# Interfaces.net
KiCad netlist of a schematic drawn in Altium Designer
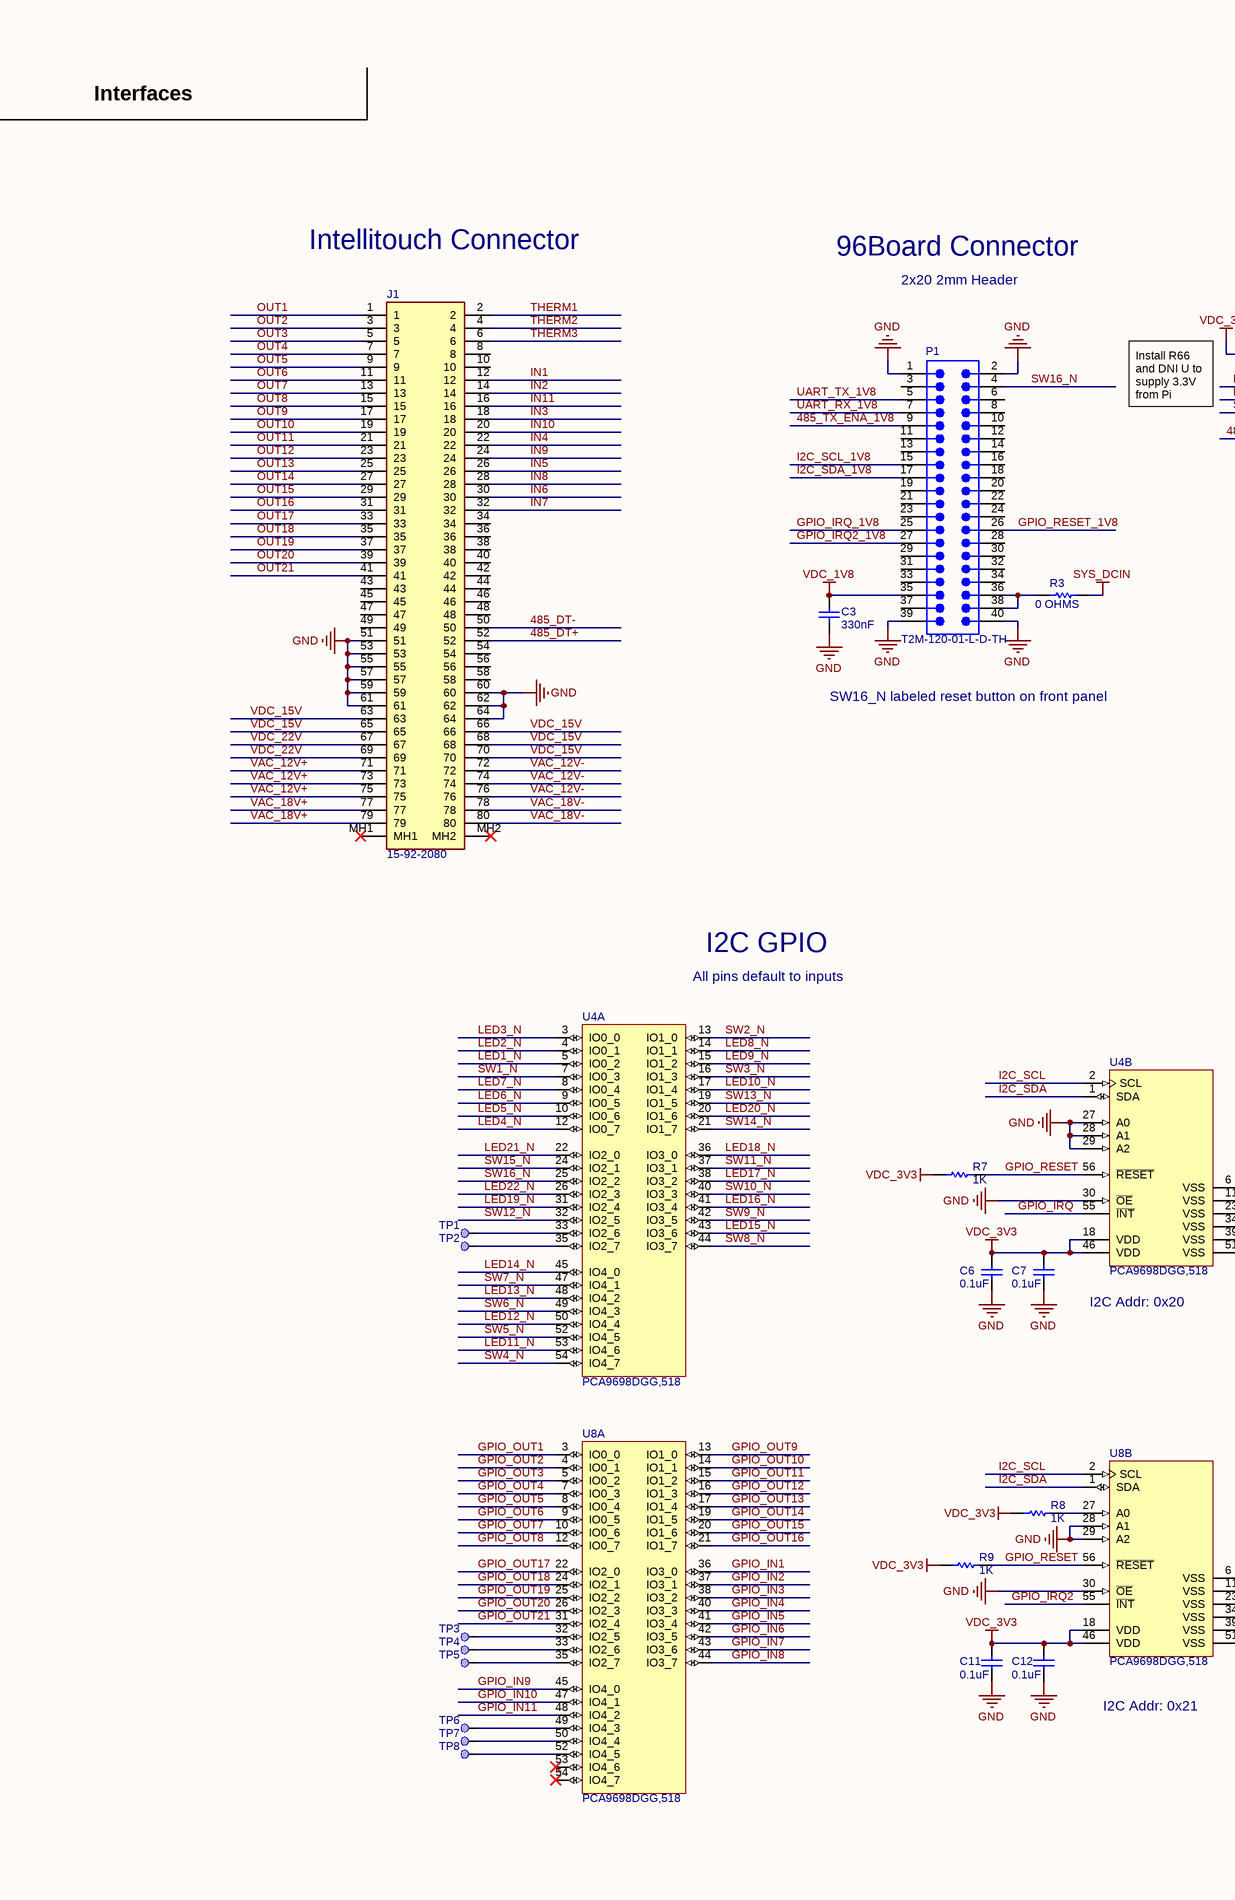
[diagram p0: Interfaces.SchDoc, left]
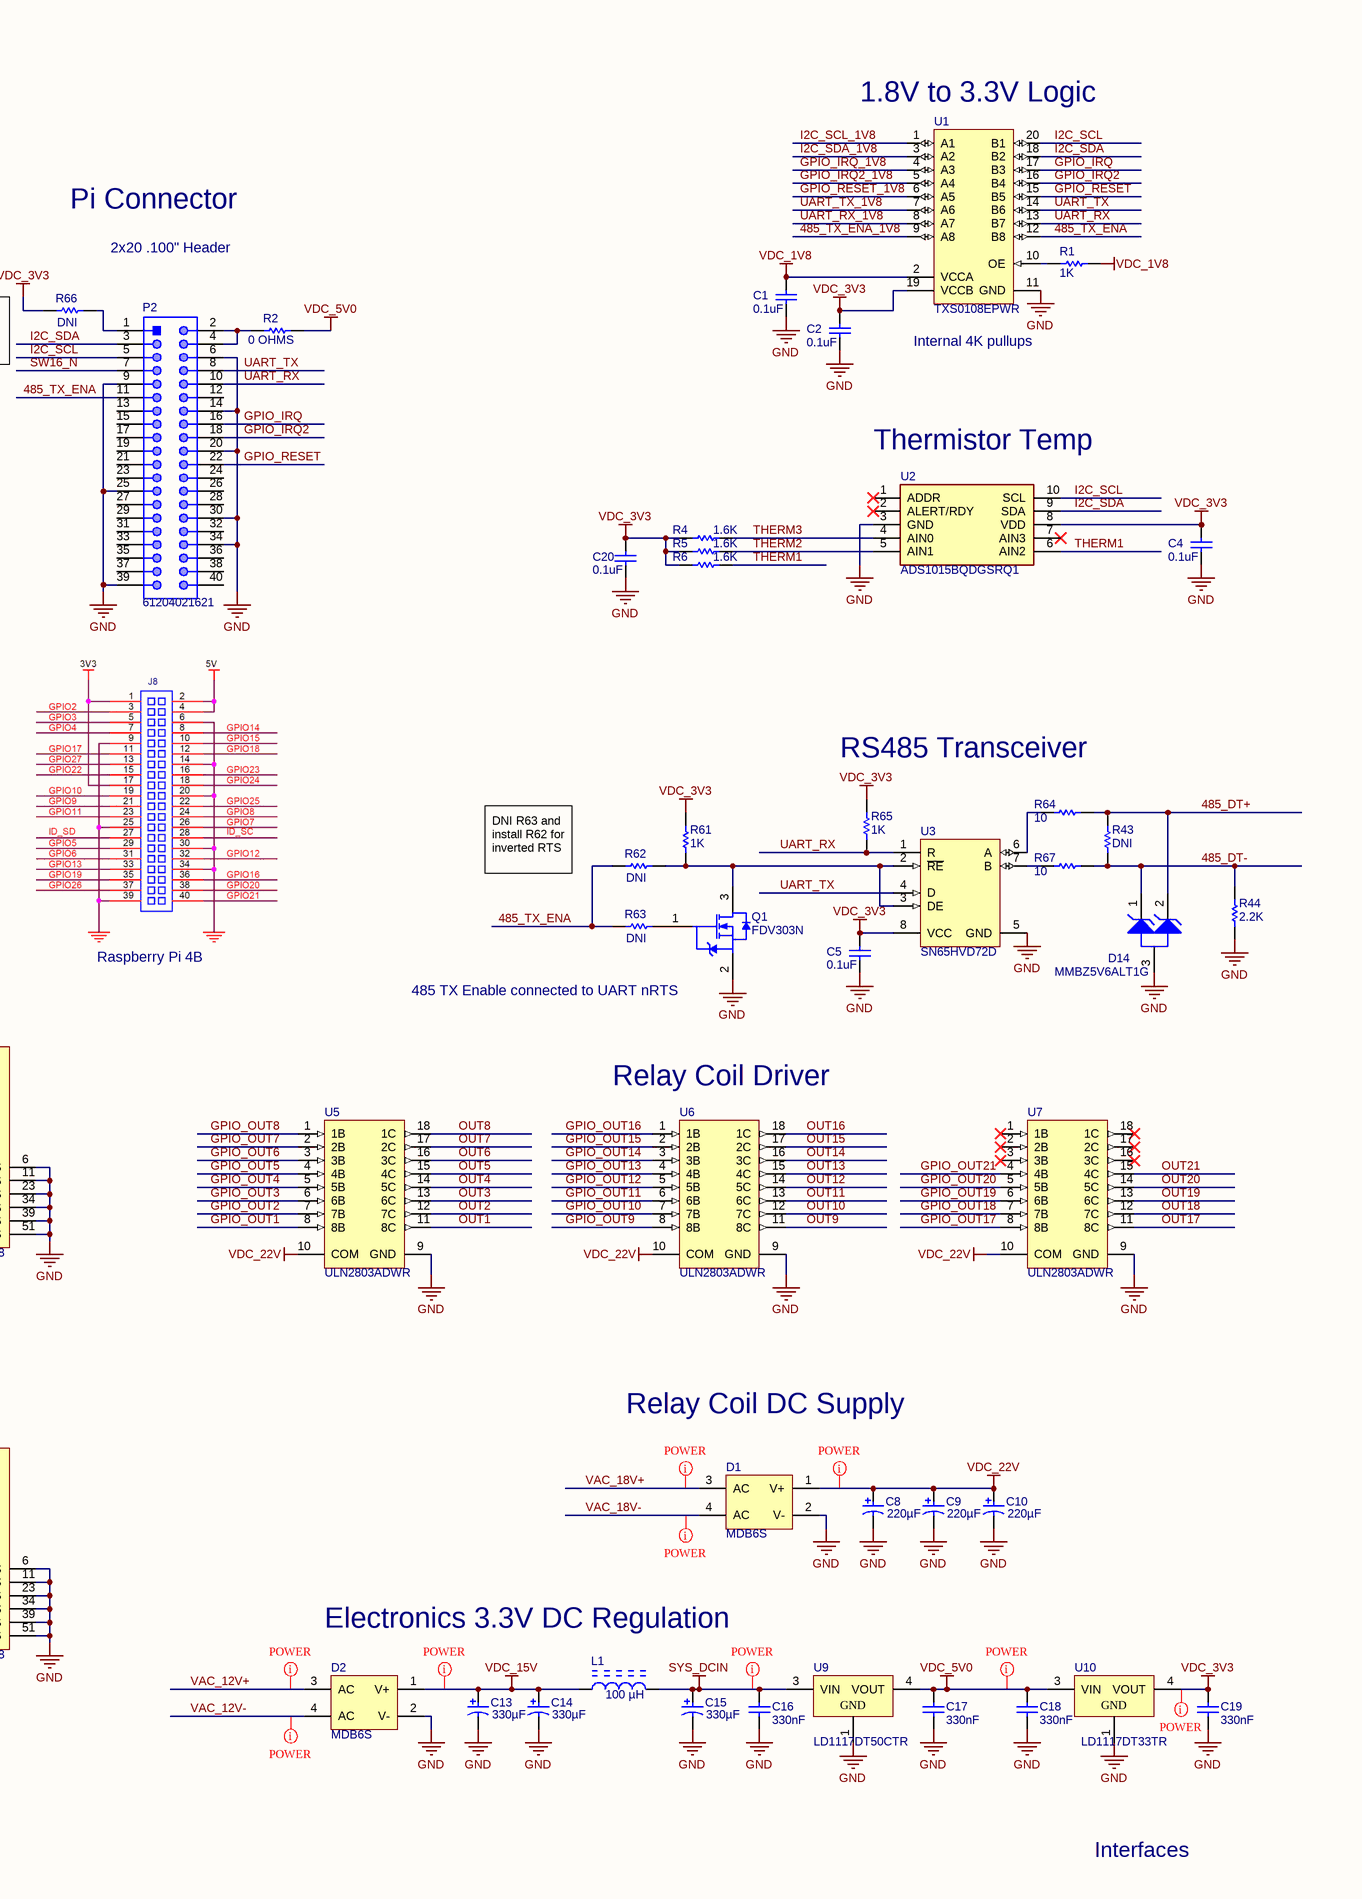
[diagram p1: Interfaces.SchDoc, right]

(export (version "E")
  (design (tool "Eeschema 10.0.6"))
  (components
    (comp (ref "C1")
      (value "0.1uF")
      (footprint "CAPC1608X87X35NL15T15")
      (fields (field (name "PART NUMBER") "C0603X104K5RACTU") (field (name "MANUFACTURER") "Kemet"))
      (libsource (lib "Altium Content Vault") (part "CAP"))
    )
    (comp (ref "C2")
      (value "0.1uF")
      (footprint "CAPC1608X87X35NL15T15")
      (fields (field (name "PART NUMBER") "C0603X104K5RACTU") (field (name "MANUFACTURER") "Kemet"))
      (libsource (lib "Altium Content Vault") (part "CAP"))
    )
    (comp (ref "C3")
      (value "330nF")
      (footprint "CAPC0805(2012)100_M")
      (description "CAP 330nF 50V ±10% 0805 (2012 Metric) Thickness 1mm SMD")
      (fields (field (name "TOLERANCE") "Â±10%") (field (name "Comment") "CAP 330nF 50V 0805(2012)"))
      (libsource (lib "Altium Content Vault") (part "CAP"))
    )
    (comp (ref "C4")
      (value "0.1uF")
      (footprint "CAPC1608X87X35NL15T15")
      (fields (field (name "PART NUMBER") "C0603X104K5RACTU") (field (name "MANUFACTURER") "Kemet"))
      (libsource (lib "Altium Content Vault") (part "CAP"))
    )
    (comp (ref "C5")
      (value "0.1uF")
      (footprint "CAPC1608X87X35NL15T15")
      (fields (field (name "PART NUMBER") "C0603X104K5RACTU") (field (name "MANUFACTURER") "Kemet"))
      (libsource (lib "Altium Content Vault") (part "CAP"))
    )
    (comp (ref "C6")
      (value "0.1uF")
      (footprint "CAPC1608X87X35NL15T15")
      (fields (field (name "PART NUMBER") "C0603X104K5RACTU") (field (name "MANUFACTURER") "Kemet"))
      (libsource (lib "Altium Content Vault") (part "CAP"))
    )
    (comp (ref "C7")
      (value "0.1uF")
      (footprint "CAPC1608X87X35NL15T15")
      (fields (field (name "PART NUMBER") "C0603X104K5RACTU") (field (name "MANUFACTURER") "Kemet"))
      (libsource (lib "Altium Content Vault") (part "CAP"))
    )
    (comp (ref "C8")
      (value "EEE-1HA221P")
      (footprint "PNSC-EEE-1HA221P_L")
      (fields (field (name "MANUFACTURER") "Panasonic") (field (name "CAPACITANCE") "220µF"))
      (libsource (lib "Altium Content Vault") (part "CAP-P-2"))
    )
    (comp (ref "C9")
      (value "EEE-1HA221P")
      (footprint "PNSC-EEE-1HA221P_L")
      (fields (field (name "MANUFACTURER") "Panasonic") (field (name "CAPACITANCE") "220µF"))
      (libsource (lib "Altium Content Vault") (part "CAP-P-2"))
    )
    (comp (ref "C10")
      (value "EEE-1HA221P")
      (footprint "PNSC-EEE-1HA221P_L")
      (fields (field (name "MANUFACTURER") "Panasonic") (field (name "CAPACITANCE") "220µF"))
      (libsource (lib "Altium Content Vault") (part "CAP-P-2"))
    )
    (comp (ref "C11")
      (value "0.1uF")
      (footprint "CAPC1608X87X35NL15T15")
      (fields (field (name "PART NUMBER") "C0603X104K5RACTU") (field (name "MANUFACTURER") "Kemet"))
      (libsource (lib "Altium Content Vault") (part "CAP"))
    )
    (comp (ref "C12")
      (value "0.1uF")
      (footprint "CAPC1608X87X35NL15T15")
      (fields (field (name "PART NUMBER") "C0603X104K5RACTU") (field (name "MANUFACTURER") "Kemet"))
      (libsource (lib "Altium Content Vault") (part "CAP"))
    )
    (comp (ref "C13")
      (value "EEE-FK1V331P")
      (footprint "PNSC-EEE-FK1V331P_L")
      (description "Aluminum Electrolytic Capacitor, 330 uF, 35 V, -55 to 105 degC, 2-Pin CAPAE, RoHS, Tape and Reel")
      (fields (field (name "CAPACITANCE") "330µF") (field (name "MANUFACTURER") "Panasonic"))
      (libsource (lib "Altium Content Vault") (part "CAP-P-2"))
    )
    (comp (ref "C14")
      (value "EEE-FK1V331P")
      (footprint "PNSC-EEE-FK1V331P_L")
      (description "Aluminum Electrolytic Capacitor, 330 uF, 35 V, -55 to 105 degC, 2-Pin CAPAE, RoHS, Tape and Reel")
      (fields (field (name "CAPACITANCE") "330µF") (field (name "MANUFACTURER") "Panasonic"))
      (libsource (lib "Altium Content Vault") (part "CAP-P-2"))
    )
    (comp (ref "C15")
      (value "EEE-FK1V331P")
      (footprint "PNSC-EEE-FK1V331P_L")
      (description "Aluminum Electrolytic Capacitor, 330 uF, 35 V, -55 to 105 degC, 2-Pin CAPAE, RoHS, Tape and Reel")
      (fields (field (name "CAPACITANCE") "330µF") (field (name "MANUFACTURER") "Panasonic"))
      (libsource (lib "Altium Content Vault") (part "CAP-P-2"))
    )
    (comp (ref "C16")
      (value "330nF")
      (footprint "CAPC0805(2012)100_M")
      (description "CAP 330nF 50V ±10% 0805 (2012 Metric) Thickness 1mm SMD")
      (fields (field (name "TOLERANCE") "Â±10%") (field (name "Comment") "CAP 330nF 50V 0805(2012)"))
      (libsource (lib "Altium Content Vault") (part "CAP"))
    )
    (comp (ref "C17")
      (value "330nF")
      (footprint "CAPC0805(2012)100_M")
      (description "CAP 330nF 50V ±10% 0805 (2012 Metric) Thickness 1mm SMD")
      (fields (field (name "TOLERANCE") "Â±10%") (field (name "Comment") "CAP 330nF 50V 0805(2012)"))
      (libsource (lib "Altium Content Vault") (part "CAP"))
    )
    (comp (ref "C18")
      (value "330nF")
      (footprint "CAPC0805(2012)100_M")
      (description "CAP 330nF 50V ±10% 0805 (2012 Metric) Thickness 1mm SMD")
      (fields (field (name "TOLERANCE") "Â±10%") (field (name "Comment") "CAP 330nF 50V 0805(2012)"))
      (libsource (lib "Altium Content Vault") (part "CAP"))
    )
    (comp (ref "C19")
      (value "330nF")
      (footprint "CAPC0805(2012)100_M")
      (description "CAP 330nF 50V ±10% 0805 (2012 Metric) Thickness 1mm SMD")
      (fields (field (name "TOLERANCE") "Â±10%") (field (name "Comment") "CAP 330nF 50V 0805(2012)"))
      (libsource (lib "Altium Content Vault") (part "CAP"))
    )
    (comp (ref "C20")
      (value "0.1uF")
      (footprint "CAPC1608X87X35NL15T15")
      (fields (field (name "PART NUMBER") "C0603X104K5RACTU") (field (name "MANUFACTURER") "Kemet"))
      (libsource (lib "Altium Content Vault") (part "CAP"))
    )
    (comp (ref "D1")
      (value "MDB6S")
      (footprint "FAIR-MDBXS-4_V")
      (fields (field (name "MANUFACTURER") "Fairchild Semiconductor"))
      (libsource (lib "Altium Content Vault") (part "FAIR-MDBXS-4"))
    )
    (comp (ref "D2")
      (value "MDB6S")
      (footprint "FAIR-MDBXS-4_V")
      (fields (field (name "MANUFACTURER") "Fairchild Semiconductor"))
      (libsource (lib "Altium Content Vault") (part "FAIR-MDBXS-4"))
    )
    (comp (ref "D14")
      (value "MMBZ5V6ALT1G")
      (footprint "ONSC-SOT-23-3-318-08_V")
      (fields (field (name "MANUFACTURER") "On Semiconductor"))
      (libsource (lib "Altium Content Vault") (part "ONSC-K1K2A3-3"))
    )
    (comp (ref "J1")
      (value "15-92-2080")
      (footprint "15922080")
      (description "Connector")
      (fields (field (name "MOUSER PART NUMBER") "538-15-92-2080"))
      (libsource (lib "SamacSys") (part "15-92-2080"))
    )
    (comp (ref "L1")
      (value "SRN8040-101M")
      (footprint "BOUR-SRN8040-101M_V")
      (description "Semi-Shielded Power Inductor, 100 uH, -40 to 125 degC, 2-Pin SMD, RoHS, Tape and Reel")
      (fields
        (field (name "TOLERANCE") "±20\r\n\r\n%")
        (field (name "MANUFACTURER") "Bourns")
        (field (name "INDUCTANCE") "100 µH")
      )
      (libsource (lib "Altium Content Vault") (part "IND-FERR-2"))
    )
    (comp (ref "P1")
      (value "T2M-120-01-L-D-TH")
      (footprint "SMTC-T2M-120-01-X-D-TH")
      (fields (field (name "MANUFACTURER") "Samtec"))
      (libsource (lib "Altium Content Vault") (part "SMTC-T2M-120-01-X-D"))
    )
    (comp (ref "P2")
      (value "61204021621")
      (footprint "61204021621")
      (description "Male Box Header WR-BHD, THT, Vertical, pitch 2.54 mm, 40 pins")
      (fields (field (name "MANUFACTURER") "Wurth Elektronik") (field (name "PUBLISHER") "WurthElektronik"))
      (libsource (lib "Altium Content Vault") (part "WE-CN-2P-M-R40"))
    )
    (comp (ref "Q1")
      (value "FDV303N")
      (footprint "FAIR-FDV303N-3_V")
      (fields (field (name "MANUFACTURER") "Fairchild"))
      (libsource (lib "Altium Content Vault") (part "NEMOS-GSD-3_D"))
    )
    (comp (ref "R1")
      (value "1K")
      (footprint "RESC1608X55X30ML15T15")
      (fields (field (name "PART NUMBER") "ERJ-3GEYJ102V") (field (name "MANUFACTURER") "Panasonic"))
      (libsource (lib "Altium Content Vault") (part "RES"))
    )
    (comp (ref "R2")
      (value "0 OHMS")
      (footprint "RESC1608X55X30NL15T15")
      (fields (field (name "MANUFACTURER") "Panasonic") (field (name "PART NUMBER") "ERJ-3GEY0R00V"))
      (libsource (lib "Altium Content Vault") (part "RES"))
    )
    (comp (ref "R3")
      (value "0 OHMS")
      (footprint "RESC1608X55X30NL15T15")
      (fields (field (name "MANUFACTURER") "Panasonic") (field (name "PART NUMBER") "ERJ-3GEY0R00V"))
      (libsource (lib "Altium Content Vault") (part "RES"))
    )
    (comp (ref "R4")
      (value "1.6K")
      (footprint "RESC1608X55X30ML15T15")
      (fields (field (name "PART NUMBER") "ERJ3EKF1601V") (field (name "MANUFACTURER") "Panasonic"))
      (libsource (lib "Altium Content Vault") (part "RES"))
    )
    (comp (ref "R5")
      (value "1.6K")
      (footprint "RESC1608X55X30ML15T15")
      (fields (field (name "PART NUMBER") "ERJ3EKF1601V") (field (name "MANUFACTURER") "Panasonic"))
      (libsource (lib "Altium Content Vault") (part "RES"))
    )
    (comp (ref "R6")
      (value "1.6K")
      (footprint "RESC1608X55X30ML15T15")
      (fields (field (name "PART NUMBER") "ERJ3EKF1601V") (field (name "MANUFACTURER") "Panasonic"))
      (libsource (lib "Altium Content Vault") (part "RES"))
    )
    (comp (ref "R7")
      (value "1K")
      (footprint "RESC1608X55X30ML15T15")
      (fields (field (name "PART NUMBER") "ERJ-3GEYJ102V") (field (name "MANUFACTURER") "Panasonic"))
      (libsource (lib "Altium Content Vault") (part "RES"))
    )
    (comp (ref "R8")
      (value "1K")
      (footprint "RESC1608X55X30ML15T15")
      (fields (field (name "PART NUMBER") "ERJ-3GEYJ102V") (field (name "MANUFACTURER") "Panasonic"))
      (libsource (lib "Altium Content Vault") (part "RES"))
    )
    (comp (ref "R9")
      (value "1K")
      (footprint "RESC1608X55X30ML15T15")
      (fields (field (name "PART NUMBER") "ERJ-3GEYJ102V") (field (name "MANUFACTURER") "Panasonic"))
      (libsource (lib "Altium Content Vault") (part "RES"))
    )
    (comp (ref "R43")
      (value "DNI")
      (footprint "RESC1608X55X30LL20T20")
      (fields (field (name "PART NUMBER") "ERA3AEB101V") (field (name "MANUFACTURER") "Panasonic"))
      (libsource (lib "Altium Content Vault") (part "RES"))
    )
    (comp (ref "R44")
      (value "2.2K")
      (footprint "RESC1005X40X25LL05T05")
      (fields (field (name "MANUFACTURER") "Panasonic"))
      (libsource (lib "Altium Content Vault") (part "RES-2"))
    )
    (comp (ref "R61")
      (value "1K")
      (footprint "RESC1608X55X30ML15T15")
      (fields (field (name "PART NUMBER") "ERJ-3GEYJ102V") (field (name "MANUFACTURER") "Panasonic"))
      (libsource (lib "Altium Content Vault") (part "RES"))
    )
    (comp (ref "R62")
      (value "DNI")
      (footprint "RESC1608X55X30NL15T15")
      (fields (field (name "MANUFACTURER") "Panasonic") (field (name "PART NUMBER") "ERJ-3GEY0R00V"))
      (libsource (lib "Altium Content Vault") (part "RES"))
    )
    (comp (ref "R63")
      (value "DNI")
      (footprint "RESC1608X55X30NL15T15")
      (fields (field (name "MANUFACTURER") "Panasonic") (field (name "PART NUMBER") "ERJ-3GEY0R00V"))
      (libsource (lib "Altium Content Vault") (part "RES"))
    )
    (comp (ref "R64")
      (value "10")
      (footprint "RESC1608X55X30ML15T15")
      (fields (field (name "MANUFACTURER") "Panasonic") (field (name "PART NUMBER") "ERJ-3EKF10R0V"))
      (libsource (lib "Altium Content Vault") (part "RES"))
    )
    (comp (ref "R65")
      (value "1K")
      (footprint "RESC1608X55X30ML15T15")
      (fields (field (name "PART NUMBER") "ERJ-3GEYJ102V") (field (name "MANUFACTURER") "Panasonic"))
      (libsource (lib "Altium Content Vault") (part "RES"))
    )
    (comp (ref "R66")
      (value "DNI")
      (footprint "RESC1608X55X30NL15T15")
      (fields (field (name "MANUFACTURER") "Panasonic") (field (name "PART NUMBER") "ERJ-3GEY0R00V"))
      (libsource (lib "Altium Content Vault") (part "RES"))
    )
    (comp (ref "R67")
      (value "10")
      (footprint "RESC1608X55X30ML15T15")
      (fields (field (name "MANUFACTURER") "Panasonic") (field (name "PART NUMBER") "ERJ-3EKF10R0V"))
      (libsource (lib "Altium Content Vault") (part "RES"))
    )
    (comp (ref "TP1")
      (value "Testpoint")
      (footprint "TP/SMT")
      (description "TEST POINT")
      (libsource (lib "intellitouch") (part "TP"))
    )
    (comp (ref "TP2")
      (value "Testpoint")
      (footprint "TP/SMT")
      (description "TEST POINT")
      (libsource (lib "intellitouch") (part "TP"))
    )
    (comp (ref "TP3")
      (value "Testpoint")
      (footprint "TP/SMT")
      (description "TEST POINT")
      (libsource (lib "intellitouch") (part "TP"))
    )
    (comp (ref "TP4")
      (value "Testpoint")
      (footprint "TP/SMT")
      (description "TEST POINT")
      (libsource (lib "intellitouch") (part "TP"))
    )
    (comp (ref "TP5")
      (value "Testpoint")
      (footprint "TP/SMT")
      (description "TEST POINT")
      (libsource (lib "intellitouch") (part "TP"))
    )
    (comp (ref "TP6")
      (value "Testpoint")
      (footprint "TP/SMT")
      (description "TEST POINT")
      (libsource (lib "intellitouch") (part "TP"))
    )
    (comp (ref "TP7")
      (value "Testpoint")
      (footprint "TP/SMT")
      (description "TEST POINT")
      (libsource (lib "intellitouch") (part "TP"))
    )
    (comp (ref "TP8")
      (value "Testpoint")
      (footprint "TP/SMT")
      (description "TEST POINT")
      (libsource (lib "intellitouch") (part "TP"))
    )
    (comp (ref "U1")
      (value "TXS0108EPWR")
      (footprint "PW0020A_M")
      (fields (field (name "MANUFACTURER") "Texas Instruments"))
      (libsource (lib "Altium Content Vault") (part "TI-TXS0108EPWR-SOP-20"))
    )
    (comp (ref "U2")
      (value "ADS1015BQDGSRQ1")
      (footprint "SamacSys:SOP50P490X110-10N")
      (description "Integrated Circuit")
      (fields (field (name "MOUSER PART NUMBER") "595-ADS1015BQDGSRQ1"))
      (libsource (lib "*") (part "ADS1015BQDGSRQ1"))
    )
    (comp (ref "U3")
      (value "SN65HVD72D")
      (footprint "D0008A_M")
      (description "3.3 V Supply RS-485 with IEC ESD Protection, 0.25 Mbps, -40 to 125 degC, 8-Pin SOIC, RoHS, Tube")
      (fields (field (name "MANUFACTURER") "Texas Instruments"))
      (libsource (lib "Altium Content Vault") (part "TI-SN65HVD7X-SOIC_D-8"))
    )
    (comp (ref "U4")
      (value "PCA9698DGG,518")
      (footprint "NXP-SOT364-1_M")
      (fields (field (name "MANUFACTURER") "NXP Semiconductors"))
      (libsource (lib "Altium Content Vault") (part "NXP-PCA9505_06DGG-TSSOP56"))
    )
    (comp (ref "U5")
      (value "ULN2803ADWR")
      (footprint "DW0018A_L")
      (fields (field (name "MANUFACTURER") "Texas Instruments") (field (name "PARTNUMBER") "ULN2803A"))
      (libsource (lib "Altium Content Vault") (part "TI-ULN2803A-SOIC_DW-18"))
    )
    (comp (ref "U6")
      (value "ULN2803ADWR")
      (footprint "DW0018A_L")
      (fields (field (name "MANUFACTURER") "Texas Instruments") (field (name "PARTNUMBER") "ULN2803A"))
      (libsource (lib "Altium Content Vault") (part "TI-ULN2803A-SOIC_DW-18"))
    )
    (comp (ref "U7")
      (value "ULN2803ADWR")
      (footprint "DW0018A_L")
      (fields (field (name "MANUFACTURER") "Texas Instruments") (field (name "PARTNUMBER") "ULN2803A"))
      (libsource (lib "Altium Content Vault") (part "TI-ULN2803A-SOIC_DW-18"))
    )
    (comp (ref "U8")
      (value "PCA9698DGG,518")
      (footprint "NXP-SOT364-1_M")
      (fields (field (name "MANUFACTURER") "NXP Semiconductors"))
      (libsource (lib "Altium Content Vault") (part "NXP-PCA9505_06DGG-TSSOP56"))
    )
    (comp (ref "U9")
      (value "LD1117DT50CTR")
      (footprint "TO-252_N")
      (description "Fixed Low Drop Positive Voltage Regulator, 5V, 3-Pin DPAK, Tape and Reel")
      (libsource (lib "Altium Content Vault") (part "PM-REG-LD1117-SOT3"))
    )
    (comp (ref "U10")
      (value "LD1117DT33TR")
      (footprint "TO-252_N")
      (description "Fixed Low Drop Positive Voltage Regulator, 3.3V, 3-Pin DPAK, Tape and Reel")
      (libsource (lib "Altium Content Vault") (part "PM-REG-LD1117-SOT3"))
    )
  )
  (nets
    (net (code "1") (name "/485_DT+") (class "Default")
      (node (ref "D14") (pin "2") (pinfunction "K2_2") (pintype "passive"))
      (node (ref "J1") (pin "52") (pinfunction "52_52") (pintype "passive"))
      (node (ref "R43") (pin "2") (pinfunction "2_2") (pintype "passive"))
      (node (ref "R64") (pin "2") (pinfunction "2_2") (pintype "passive"))
    )
    (net (code "2") (name "/485_DT-") (class "Default")
      (node (ref "D14") (pin "1") (pinfunction "K1_1") (pintype "passive"))
      (node (ref "J1") (pin "50") (pinfunction "50_50") (pintype "passive"))
      (node (ref "R43") (pin "1") (pinfunction "1_1") (pintype "passive"))
      (node (ref "R44") (pin "2") (pinfunction "2_2") (pintype "passive"))
      (node (ref "R67") (pin "2") (pinfunction "2_2") (pintype "passive"))
    )
    (net (code "3") (name "/485_TX_ENA") (class "Default")
      (node (ref "P2") (pin "11") (pinfunction "11_11") (pintype "passive"))
      (node (ref "R62") (pin "1") (pinfunction "1_1") (pintype "passive"))
      (node (ref "R63") (pin "1") (pinfunction "1_1") (pintype "passive"))
      (node (ref "U1") (pin "12") (pinfunction "B8_12") (pintype "bidirectional"))
    )
    (net (code "4") (name "/485_TX_ENA_1V8") (class "Default")
      (node (ref "P1") (pin "9") (pinfunction "9_9") (pintype "passive"))
      (node (ref "U1") (pin "9") (pinfunction "A8_9") (pintype "bidirectional"))
    )
    (net (code "5") (name "/GPIO_IN1") (class "Default")
      (node (ref "U8") (pin "36") (pinfunction "IO3_0_36") (pintype "bidirectional"))
    )
    (net (code "6") (name "/GPIO_IN2") (class "Default")
      (node (ref "U8") (pin "37") (pinfunction "IO3_1_37") (pintype "bidirectional"))
    )
    (net (code "7") (name "/GPIO_IN3") (class "Default")
      (node (ref "U8") (pin "38") (pinfunction "IO3_2_38") (pintype "bidirectional"))
    )
    (net (code "8") (name "/GPIO_IN4") (class "Default")
      (node (ref "U8") (pin "40") (pinfunction "IO3_3_40") (pintype "bidirectional"))
    )
    (net (code "9") (name "/GPIO_IN5") (class "Default")
      (node (ref "U8") (pin "41") (pinfunction "IO3_4_41") (pintype "bidirectional"))
    )
    (net (code "10") (name "/GPIO_IN6") (class "Default")
      (node (ref "U8") (pin "42") (pinfunction "IO3_5_42") (pintype "bidirectional"))
    )
    (net (code "11") (name "/GPIO_IN7") (class "Default")
      (node (ref "U8") (pin "43") (pinfunction "IO3_6_43") (pintype "bidirectional"))
    )
    (net (code "12") (name "/GPIO_IN8") (class "Default")
      (node (ref "U8") (pin "44") (pinfunction "IO3_7_44") (pintype "bidirectional"))
    )
    (net (code "13") (name "/GPIO_IN9") (class "Default")
      (node (ref "U8") (pin "45") (pinfunction "IO4_0_45") (pintype "bidirectional"))
    )
    (net (code "14") (name "/GPIO_IN10") (class "Default")
      (node (ref "U8") (pin "47") (pinfunction "IO4_1_47") (pintype "bidirectional"))
    )
    (net (code "15") (name "/GPIO_IN11") (class "Default")
      (node (ref "U8") (pin "48") (pinfunction "IO4_2_48") (pintype "bidirectional"))
    )
    (net (code "16") (name "/GPIO_IRQ") (class "Default")
      (node (ref "P2") (pin "16") (pinfunction "16_16") (pintype "passive"))
      (node (ref "U1") (pin "17") (pinfunction "B3_17") (pintype "bidirectional"))
      (node (ref "U4") (pin "55") (pinfunction "~{INT}_55") (pintype "open_collector"))
    )
    (net (code "17") (name "/GPIO_IRQ2") (class "Default")
      (node (ref "P2") (pin "18") (pinfunction "18_18") (pintype "passive"))
      (node (ref "U1") (pin "16") (pinfunction "B4_16") (pintype "bidirectional"))
      (node (ref "U8") (pin "55") (pinfunction "~{INT}_55") (pintype "open_collector"))
    )
    (net (code "18") (name "/GPIO_IRQ2_1V8") (class "Default")
      (node (ref "P1") (pin "27") (pinfunction "27_27") (pintype "passive"))
      (node (ref "U1") (pin "5") (pinfunction "A4_5") (pintype "bidirectional"))
    )
    (net (code "19") (name "/GPIO_IRQ_1V8") (class "Default")
      (node (ref "P1") (pin "25") (pinfunction "25_25") (pintype "passive"))
      (node (ref "U1") (pin "4") (pinfunction "A3_4") (pintype "bidirectional"))
    )
    (net (code "20") (name "/GPIO_OUT1") (class "Default")
      (node (ref "U5") (pin "8") (pinfunction "8B_8") (pintype "input"))
      (node (ref "U8") (pin "3") (pinfunction "IO0_0_3") (pintype "bidirectional"))
    )
    (net (code "21") (name "/GPIO_OUT2") (class "Default")
      (node (ref "U5") (pin "7") (pinfunction "7B_7") (pintype "input"))
      (node (ref "U8") (pin "4") (pinfunction "IO0_1_4") (pintype "bidirectional"))
    )
    (net (code "22") (name "/GPIO_OUT3") (class "Default")
      (node (ref "U5") (pin "6") (pinfunction "6B_6") (pintype "input"))
      (node (ref "U8") (pin "5") (pinfunction "IO0_2_5") (pintype "bidirectional"))
    )
    (net (code "23") (name "/GPIO_OUT4") (class "Default")
      (node (ref "U5") (pin "5") (pinfunction "5B_5") (pintype "input"))
      (node (ref "U8") (pin "7") (pinfunction "IO0_3_7") (pintype "bidirectional"))
    )
    (net (code "24") (name "/GPIO_OUT5") (class "Default")
      (node (ref "U5") (pin "4") (pinfunction "4B_4") (pintype "input"))
      (node (ref "U8") (pin "8") (pinfunction "IO0_4_8") (pintype "bidirectional"))
    )
    (net (code "25") (name "/GPIO_OUT6") (class "Default")
      (node (ref "U5") (pin "3") (pinfunction "3B_3") (pintype "input"))
      (node (ref "U8") (pin "9") (pinfunction "IO0_5_9") (pintype "bidirectional"))
    )
    (net (code "26") (name "/GPIO_OUT7") (class "Default")
      (node (ref "U5") (pin "2") (pinfunction "2B_2") (pintype "input"))
      (node (ref "U8") (pin "10") (pinfunction "IO0_6_10") (pintype "bidirectional"))
    )
    (net (code "27") (name "/GPIO_OUT8") (class "Default")
      (node (ref "U5") (pin "1") (pinfunction "1B_1") (pintype "input"))
      (node (ref "U8") (pin "12") (pinfunction "IO0_7_12") (pintype "bidirectional"))
    )
    (net (code "28") (name "/GPIO_OUT9") (class "Default")
      (node (ref "U6") (pin "8") (pinfunction "8B_8") (pintype "input"))
      (node (ref "U8") (pin "13") (pinfunction "IO1_0_13") (pintype "bidirectional"))
    )
    (net (code "29") (name "/GPIO_OUT10") (class "Default")
      (node (ref "U6") (pin "7") (pinfunction "7B_7") (pintype "input"))
      (node (ref "U8") (pin "14") (pinfunction "IO1_1_14") (pintype "bidirectional"))
    )
    (net (code "30") (name "/GPIO_OUT11") (class "Default")
      (node (ref "U6") (pin "6") (pinfunction "6B_6") (pintype "input"))
      (node (ref "U8") (pin "15") (pinfunction "IO1_2_15") (pintype "bidirectional"))
    )
    (net (code "31") (name "/GPIO_OUT12") (class "Default")
      (node (ref "U6") (pin "5") (pinfunction "5B_5") (pintype "input"))
      (node (ref "U8") (pin "16") (pinfunction "IO1_3_16") (pintype "bidirectional"))
    )
    (net (code "32") (name "/GPIO_OUT13") (class "Default")
      (node (ref "U6") (pin "4") (pinfunction "4B_4") (pintype "input"))
      (node (ref "U8") (pin "17") (pinfunction "IO1_4_17") (pintype "bidirectional"))
    )
    (net (code "33") (name "/GPIO_OUT14") (class "Default")
      (node (ref "U6") (pin "3") (pinfunction "3B_3") (pintype "input"))
      (node (ref "U8") (pin "19") (pinfunction "IO1_5_19") (pintype "bidirectional"))
    )
    (net (code "34") (name "/GPIO_OUT15") (class "Default")
      (node (ref "U6") (pin "2") (pinfunction "2B_2") (pintype "input"))
      (node (ref "U8") (pin "20") (pinfunction "IO1_6_20") (pintype "bidirectional"))
    )
    (net (code "35") (name "/GPIO_OUT16") (class "Default")
      (node (ref "U6") (pin "1") (pinfunction "1B_1") (pintype "input"))
      (node (ref "U8") (pin "21") (pinfunction "IO1_7_21") (pintype "bidirectional"))
    )
    (net (code "36") (name "/GPIO_OUT17") (class "Default")
      (node (ref "U7") (pin "8") (pinfunction "8B_8") (pintype "input"))
      (node (ref "U8") (pin "22") (pinfunction "IO2_0_22") (pintype "bidirectional"))
    )
    (net (code "37") (name "/GPIO_OUT18") (class "Default")
      (node (ref "U7") (pin "7") (pinfunction "7B_7") (pintype "input"))
      (node (ref "U8") (pin "24") (pinfunction "IO2_1_24") (pintype "bidirectional"))
    )
    (net (code "38") (name "/GPIO_OUT19") (class "Default")
      (node (ref "U7") (pin "6") (pinfunction "6B_6") (pintype "input"))
      (node (ref "U8") (pin "25") (pinfunction "IO2_2_25") (pintype "bidirectional"))
    )
    (net (code "39") (name "/GPIO_OUT20") (class "Default")
      (node (ref "U7") (pin "5") (pinfunction "5B_5") (pintype "input"))
      (node (ref "U8") (pin "26") (pinfunction "IO2_3_26") (pintype "bidirectional"))
    )
    (net (code "40") (name "/GPIO_OUT21") (class "Default")
      (node (ref "U7") (pin "4") (pinfunction "4B_4") (pintype "input"))
      (node (ref "U8") (pin "31") (pinfunction "IO2_4_31") (pintype "bidirectional"))
    )
    (net (code "41") (name "/GPIO_RESET") (class "Default")
      (node (ref "P2") (pin "22") (pinfunction "22_22") (pintype "passive"))
      (node (ref "R7") (pin "2") (pinfunction "2_2") (pintype "passive"))
      (node (ref "R9") (pin "2") (pinfunction "2_2") (pintype "passive"))
      (node (ref "U1") (pin "15") (pinfunction "B5_15") (pintype "bidirectional"))
      (node (ref "U4") (pin "56") (pinfunction "~{RESET}_56") (pintype "input"))
      (node (ref "U8") (pin "56") (pinfunction "~{RESET}_56") (pintype "input"))
    )
    (net (code "42") (name "/GPIO_RESET_1V8") (class "Default")
      (node (ref "P1") (pin "26") (pinfunction "26_26") (pintype "passive"))
      (node (ref "U1") (pin "6") (pinfunction "A5_6") (pintype "bidirectional"))
    )
    (net (code "43") (name "/I2C_SCL") (class "Default")
      (node (ref "P2") (pin "5") (pinfunction "5_5") (pintype "passive"))
      (node (ref "U1") (pin "20") (pinfunction "B1_20") (pintype "bidirectional"))
      (node (ref "U2") (pin "10") (pinfunction "SCL_10") (pintype "passive"))
      (node (ref "U4") (pin "2") (pinfunction "SCL_2") (pintype "input"))
      (node (ref "U8") (pin "2") (pinfunction "SCL_2") (pintype "input"))
    )
    (net (code "44") (name "/I2C_SCL_1V8") (class "Default")
      (node (ref "P1") (pin "15") (pinfunction "15_15") (pintype "passive"))
      (node (ref "U1") (pin "1") (pinfunction "A1_1") (pintype "bidirectional"))
    )
    (net (code "45") (name "/I2C_SDA") (class "Default")
      (node (ref "P2") (pin "3") (pinfunction "3_3") (pintype "passive"))
      (node (ref "U1") (pin "18") (pinfunction "B2_18") (pintype "bidirectional"))
      (node (ref "U2") (pin "9") (pinfunction "SDA_9") (pintype "passive"))
      (node (ref "U4") (pin "1") (pinfunction "SDA_1") (pintype "bidirectional"))
      (node (ref "U8") (pin "1") (pinfunction "SDA_1") (pintype "bidirectional"))
    )
    (net (code "46") (name "/I2C_SDA_1V8") (class "Default")
      (node (ref "P1") (pin "17") (pinfunction "17_17") (pintype "passive"))
      (node (ref "U1") (pin "3") (pinfunction "A2_3") (pintype "bidirectional"))
    )
    (net (code "47") (name "/IN1") (class "Default")
      (node (ref "J1") (pin "12") (pinfunction "12_12") (pintype "passive"))
    )
    (net (code "48") (name "/IN2") (class "Default")
      (node (ref "J1") (pin "14") (pinfunction "14_14") (pintype "passive"))
    )
    (net (code "49") (name "/IN3") (class "Default")
      (node (ref "J1") (pin "18") (pinfunction "18_18") (pintype "passive"))
    )
    (net (code "50") (name "/IN4") (class "Default")
      (node (ref "J1") (pin "22") (pinfunction "22_22") (pintype "passive"))
    )
    (net (code "51") (name "/IN5") (class "Default")
      (node (ref "J1") (pin "26") (pinfunction "26_26") (pintype "passive"))
    )
    (net (code "52") (name "/IN6") (class "Default")
      (node (ref "J1") (pin "30") (pinfunction "30_30") (pintype "passive"))
    )
    (net (code "53") (name "/IN7") (class "Default")
      (node (ref "J1") (pin "32") (pinfunction "32_32") (pintype "passive"))
    )
    (net (code "54") (name "/IN8") (class "Default")
      (node (ref "J1") (pin "28") (pinfunction "28_28") (pintype "passive"))
    )
    (net (code "55") (name "/IN9") (class "Default")
      (node (ref "J1") (pin "24") (pinfunction "24_24") (pintype "passive"))
    )
    (net (code "56") (name "/IN10") (class "Default")
      (node (ref "J1") (pin "20") (pinfunction "20_20") (pintype "passive"))
    )
    (net (code "57") (name "/IN11") (class "Default")
      (node (ref "J1") (pin "16") (pinfunction "16_16") (pintype "passive"))
    )
    (net (code "58") (name "/LED1_N") (class "Default")
      (node (ref "U4") (pin "5") (pinfunction "IO0_2_5") (pintype "bidirectional"))
    )
    (net (code "59") (name "/LED2_N") (class "Default")
      (node (ref "U4") (pin "4") (pinfunction "IO0_1_4") (pintype "bidirectional"))
    )
    (net (code "60") (name "/LED3_N") (class "Default")
      (node (ref "U4") (pin "3") (pinfunction "IO0_0_3") (pintype "bidirectional"))
    )
    (net (code "61") (name "/LED4_N") (class "Default")
      (node (ref "U4") (pin "12") (pinfunction "IO0_7_12") (pintype "bidirectional"))
    )
    (net (code "62") (name "/LED5_N") (class "Default")
      (node (ref "U4") (pin "10") (pinfunction "IO0_6_10") (pintype "bidirectional"))
    )
    (net (code "63") (name "/LED6_N") (class "Default")
      (node (ref "U4") (pin "9") (pinfunction "IO0_5_9") (pintype "bidirectional"))
    )
    (net (code "64") (name "/LED7_N") (class "Default")
      (node (ref "U4") (pin "8") (pinfunction "IO0_4_8") (pintype "bidirectional"))
    )
    (net (code "65") (name "/LED8_N") (class "Default")
      (node (ref "U4") (pin "14") (pinfunction "IO1_1_14") (pintype "bidirectional"))
    )
    (net (code "66") (name "/LED9_N") (class "Default")
      (node (ref "U4") (pin "15") (pinfunction "IO1_2_15") (pintype "bidirectional"))
    )
    (net (code "67") (name "/LED10_N") (class "Default")
      (node (ref "U4") (pin "17") (pinfunction "IO1_4_17") (pintype "bidirectional"))
    )
    (net (code "68") (name "/LED11_N") (class "Default")
      (node (ref "U4") (pin "53") (pinfunction "IO4_6_53") (pintype "bidirectional"))
    )
    (net (code "69") (name "/LED12_N") (class "Default")
      (node (ref "U4") (pin "50") (pinfunction "IO4_4_50") (pintype "bidirectional"))
    )
    (net (code "70") (name "/LED13_N") (class "Default")
      (node (ref "U4") (pin "48") (pinfunction "IO4_2_48") (pintype "bidirectional"))
    )
    (net (code "71") (name "/LED14_N") (class "Default")
      (node (ref "U4") (pin "45") (pinfunction "IO4_0_45") (pintype "bidirectional"))
    )
    (net (code "72") (name "/LED15_N") (class "Default")
      (node (ref "U4") (pin "43") (pinfunction "IO3_6_43") (pintype "bidirectional"))
    )
    (net (code "73") (name "/LED16_N") (class "Default")
      (node (ref "U4") (pin "41") (pinfunction "IO3_4_41") (pintype "bidirectional"))
    )
    (net (code "74") (name "/LED17_N") (class "Default")
      (node (ref "U4") (pin "38") (pinfunction "IO3_2_38") (pintype "bidirectional"))
    )
    (net (code "75") (name "/LED18_N") (class "Default")
      (node (ref "U4") (pin "36") (pinfunction "IO3_0_36") (pintype "bidirectional"))
    )
    (net (code "76") (name "/LED19_N") (class "Default")
      (node (ref "U4") (pin "31") (pinfunction "IO2_4_31") (pintype "bidirectional"))
    )
    (net (code "77") (name "/LED20_N") (class "Default")
      (node (ref "U4") (pin "20") (pinfunction "IO1_6_20") (pintype "bidirectional"))
    )
    (net (code "78") (name "/LED21_N") (class "Default")
      (node (ref "U4") (pin "22") (pinfunction "IO2_0_22") (pintype "bidirectional"))
    )
    (net (code "79") (name "/LED22_N") (class "Default")
      (node (ref "U4") (pin "26") (pinfunction "IO2_3_26") (pintype "bidirectional"))
    )
    (net (code "80") (name "/OUT1") (class "Default")
      (node (ref "J1") (pin "1") (pinfunction "1_1") (pintype "passive"))
      (node (ref "U5") (pin "11") (pinfunction "8C_11") (pintype "output"))
    )
    (net (code "81") (name "/OUT2") (class "Default")
      (node (ref "J1") (pin "3") (pinfunction "3_3") (pintype "passive"))
      (node (ref "U5") (pin "12") (pinfunction "7C_12") (pintype "output"))
    )
    (net (code "82") (name "/OUT3") (class "Default")
      (node (ref "J1") (pin "5") (pinfunction "5_5") (pintype "passive"))
      (node (ref "U5") (pin "13") (pinfunction "6C_13") (pintype "output"))
    )
    (net (code "83") (name "/OUT4") (class "Default")
      (node (ref "J1") (pin "7") (pinfunction "7_7") (pintype "passive"))
      (node (ref "U5") (pin "14") (pinfunction "5C_14") (pintype "output"))
    )
    (net (code "84") (name "/OUT5") (class "Default")
      (node (ref "J1") (pin "9") (pinfunction "9_9") (pintype "passive"))
      (node (ref "U5") (pin "15") (pinfunction "4C_15") (pintype "output"))
    )
    (net (code "85") (name "/OUT6") (class "Default")
      (node (ref "J1") (pin "11") (pinfunction "11_11") (pintype "passive"))
      (node (ref "U5") (pin "16") (pinfunction "3C_16") (pintype "output"))
    )
    (net (code "86") (name "/OUT7") (class "Default")
      (node (ref "J1") (pin "13") (pinfunction "13_13") (pintype "passive"))
      (node (ref "U5") (pin "17") (pinfunction "2C_17") (pintype "output"))
    )
    (net (code "87") (name "/OUT8") (class "Default")
      (node (ref "J1") (pin "15") (pinfunction "15_15") (pintype "passive"))
      (node (ref "U5") (pin "18") (pinfunction "1C_18") (pintype "output"))
    )
    (net (code "88") (name "/OUT9") (class "Default")
      (node (ref "J1") (pin "17") (pinfunction "17_17") (pintype "passive"))
      (node (ref "U6") (pin "11") (pinfunction "8C_11") (pintype "output"))
    )
    (net (code "89") (name "/OUT10") (class "Default")
      (node (ref "J1") (pin "19") (pinfunction "19_19") (pintype "passive"))
      (node (ref "U6") (pin "12") (pinfunction "7C_12") (pintype "output"))
    )
    (net (code "90") (name "/OUT11") (class "Default")
      (node (ref "J1") (pin "21") (pinfunction "21_21") (pintype "passive"))
      (node (ref "U6") (pin "13") (pinfunction "6C_13") (pintype "output"))
    )
    (net (code "91") (name "/OUT12") (class "Default")
      (node (ref "J1") (pin "23") (pinfunction "23_23") (pintype "passive"))
      (node (ref "U6") (pin "14") (pinfunction "5C_14") (pintype "output"))
    )
    (net (code "92") (name "/OUT13") (class "Default")
      (node (ref "J1") (pin "25") (pinfunction "25_25") (pintype "passive"))
      (node (ref "U6") (pin "15") (pinfunction "4C_15") (pintype "output"))
    )
    (net (code "93") (name "/OUT14") (class "Default")
      (node (ref "J1") (pin "27") (pinfunction "27_27") (pintype "passive"))
      (node (ref "U6") (pin "16") (pinfunction "3C_16") (pintype "output"))
    )
    (net (code "94") (name "/OUT15") (class "Default")
      (node (ref "J1") (pin "29") (pinfunction "29_29") (pintype "passive"))
      (node (ref "U6") (pin "17") (pinfunction "2C_17") (pintype "output"))
    )
    (net (code "95") (name "/OUT16") (class "Default")
      (node (ref "J1") (pin "31") (pinfunction "31_31") (pintype "passive"))
      (node (ref "U6") (pin "18") (pinfunction "1C_18") (pintype "output"))
    )
    (net (code "96") (name "/OUT17") (class "Default")
      (node (ref "J1") (pin "33") (pinfunction "33_33") (pintype "passive"))
      (node (ref "U7") (pin "11") (pinfunction "8C_11") (pintype "output"))
    )
    (net (code "97") (name "/OUT18") (class "Default")
      (node (ref "J1") (pin "35") (pinfunction "35_35") (pintype "passive"))
      (node (ref "U7") (pin "12") (pinfunction "7C_12") (pintype "output"))
    )
    (net (code "98") (name "/OUT19") (class "Default")
      (node (ref "J1") (pin "37") (pinfunction "37_37") (pintype "passive"))
      (node (ref "U7") (pin "13") (pinfunction "6C_13") (pintype "output"))
    )
    (net (code "99") (name "/OUT20") (class "Default")
      (node (ref "J1") (pin "39") (pinfunction "39_39") (pintype "passive"))
      (node (ref "U7") (pin "14") (pinfunction "5C_14") (pintype "output"))
    )
    (net (code "100") (name "/OUT21") (class "Default")
      (node (ref "J1") (pin "41") (pinfunction "41_41") (pintype "passive"))
      (node (ref "U7") (pin "15") (pinfunction "4C_15") (pintype "output"))
    )
    (net (code "101") (name "/SW1_N") (class "Default")
      (node (ref "U4") (pin "7") (pinfunction "IO0_3_7") (pintype "bidirectional"))
    )
    (net (code "102") (name "/SW2_N") (class "Default")
      (node (ref "U4") (pin "13") (pinfunction "IO1_0_13") (pintype "bidirectional"))
    )
    (net (code "103") (name "/SW3_N") (class "Default")
      (node (ref "U4") (pin "16") (pinfunction "IO1_3_16") (pintype "bidirectional"))
    )
    (net (code "104") (name "/SW4_N") (class "Default")
      (node (ref "U4") (pin "54") (pinfunction "IO4_7_54") (pintype "bidirectional"))
    )
    (net (code "105") (name "/SW5_N") (class "Default")
      (node (ref "U4") (pin "52") (pinfunction "IO4_5_52") (pintype "bidirectional"))
    )
    (net (code "106") (name "/SW6_N") (class "Default")
      (node (ref "U4") (pin "49") (pinfunction "IO4_3_49") (pintype "bidirectional"))
    )
    (net (code "107") (name "/SW7_N") (class "Default")
      (node (ref "U4") (pin "47") (pinfunction "IO4_1_47") (pintype "bidirectional"))
    )
    (net (code "108") (name "/SW8_N") (class "Default")
      (node (ref "U4") (pin "44") (pinfunction "IO3_7_44") (pintype "bidirectional"))
    )
    (net (code "109") (name "/SW9_N") (class "Default")
      (node (ref "U4") (pin "42") (pinfunction "IO3_5_42") (pintype "bidirectional"))
    )
    (net (code "110") (name "/SW10_N") (class "Default")
      (node (ref "U4") (pin "40") (pinfunction "IO3_3_40") (pintype "bidirectional"))
    )
    (net (code "111") (name "/SW11_N") (class "Default")
      (node (ref "U4") (pin "37") (pinfunction "IO3_1_37") (pintype "bidirectional"))
    )
    (net (code "112") (name "/SW12_N") (class "Default")
      (node (ref "U4") (pin "32") (pinfunction "IO2_5_32") (pintype "bidirectional"))
    )
    (net (code "113") (name "/SW13_N") (class "Default")
      (node (ref "U4") (pin "19") (pinfunction "IO1_5_19") (pintype "bidirectional"))
    )
    (net (code "114") (name "/SW14_N") (class "Default")
      (node (ref "U4") (pin "21") (pinfunction "IO1_7_21") (pintype "bidirectional"))
    )
    (net (code "115") (name "/SW15_N") (class "Default")
      (node (ref "U4") (pin "24") (pinfunction "IO2_1_24") (pintype "bidirectional"))
    )
    (net (code "116") (name "/SW16_N") (class "Default")
      (node (ref "P1") (pin "4") (pinfunction "4_4") (pintype "passive"))
      (node (ref "P2") (pin "7") (pinfunction "7_7") (pintype "passive"))
      (node (ref "U4") (pin "25") (pinfunction "IO2_2_25") (pintype "bidirectional"))
    )
    (net (code "117") (name "/THERM1") (class "Default")
      (node (ref "J1") (pin "2") (pinfunction "2_2") (pintype "passive"))
      (node (ref "R6") (pin "2") (pinfunction "2_2") (pintype "passive"))
      (node (ref "U2") (pin "6") (pinfunction "AIN2_6") (pintype "passive"))
    )
    (net (code "118") (name "/THERM2") (class "Default")
      (node (ref "J1") (pin "4") (pinfunction "4_4") (pintype "passive"))
      (node (ref "R5") (pin "2") (pinfunction "2_2") (pintype "passive"))
      (node (ref "U2") (pin "5") (pinfunction "AIN1_5") (pintype "passive"))
    )
    (net (code "119") (name "/THERM3") (class "Default")
      (node (ref "J1") (pin "6") (pinfunction "6_6") (pintype "passive"))
      (node (ref "R4") (pin "2") (pinfunction "2_2") (pintype "passive"))
      (node (ref "U2") (pin "4") (pinfunction "AIN0_4") (pintype "passive"))
    )
    (net (code "120") (name "/UART_RX") (class "Default")
      (node (ref "P2") (pin "10") (pinfunction "10_10") (pintype "passive"))
      (node (ref "R65") (pin "2") (pinfunction "2_2") (pintype "passive"))
      (node (ref "U1") (pin "13") (pinfunction "B7_13") (pintype "bidirectional"))
      (node (ref "U3") (pin "1") (pinfunction "R_1") (pintype "tri_state"))
    )
    (net (code "121") (name "/UART_RX_1V8") (class "Default")
      (node (ref "P1") (pin "7") (pinfunction "7_7") (pintype "passive"))
      (node (ref "U1") (pin "8") (pinfunction "A7_8") (pintype "bidirectional"))
    )
    (net (code "122") (name "/UART_TX") (class "Default")
      (node (ref "P2") (pin "8") (pinfunction "8_8") (pintype "passive"))
      (node (ref "U1") (pin "14") (pinfunction "B6_14") (pintype "bidirectional"))
      (node (ref "U3") (pin "4") (pinfunction "D_4") (pintype "input"))
    )
    (net (code "123") (name "/UART_TX_1V8") (class "Default")
      (node (ref "P1") (pin "5") (pinfunction "5_5") (pintype "passive"))
      (node (ref "U1") (pin "7") (pinfunction "A6_7") (pintype "bidirectional"))
    )
    (net (code "124") (name "/VAC_12V+") (class "Default")
      (node (ref "D2") (pin "3") (pinfunction "AC_3") (pintype "power_in"))
      (node (ref "J1") (pin "71") (pinfunction "71_71") (pintype "passive"))
      (node (ref "J1") (pin "73") (pinfunction "73_73") (pintype "passive"))
      (node (ref "J1") (pin "75") (pinfunction "75_75") (pintype "passive"))
    )
    (net (code "125") (name "/VAC_12V-") (class "Default")
      (node (ref "D2") (pin "4") (pinfunction "AC_4") (pintype "power_in"))
      (node (ref "J1") (pin "72") (pinfunction "72_72") (pintype "passive"))
      (node (ref "J1") (pin "74") (pinfunction "74_74") (pintype "passive"))
      (node (ref "J1") (pin "76") (pinfunction "76_76") (pintype "passive"))
    )
    (net (code "126") (name "/VAC_18V+") (class "Default")
      (node (ref "D1") (pin "3") (pinfunction "AC_3") (pintype "power_in"))
      (node (ref "J1") (pin "77") (pinfunction "77_77") (pintype "passive"))
      (node (ref "J1") (pin "79") (pinfunction "79_79") (pintype "passive"))
    )
    (net (code "127") (name "/VAC_18V-") (class "Default")
      (node (ref "D1") (pin "4") (pinfunction "AC_4") (pintype "power_in"))
      (node (ref "J1") (pin "78") (pinfunction "78_78") (pintype "passive"))
      (node (ref "J1") (pin "80") (pinfunction "80_80") (pintype "passive"))
    )
    (net (code "128") (name "GND") (class "Default")
      (node (ref "C1") (pin "1") (pinfunction "1_1") (pintype "passive"))
      (node (ref "C10") (pin "2") (pinfunction "2_2") (pintype "passive"))
      (node (ref "C11") (pin "1") (pinfunction "1_1") (pintype "passive"))
      (node (ref "C12") (pin "1") (pinfunction "1_1") (pintype "passive"))
      (node (ref "C13") (pin "2") (pinfunction "2_2") (pintype "passive"))
      (node (ref "C14") (pin "2") (pinfunction "2_2") (pintype "passive"))
      (node (ref "C15") (pin "2") (pinfunction "2_2") (pintype "passive"))
      (node (ref "C16") (pin "1") (pinfunction "1_1") (pintype "passive"))
      (node (ref "C17") (pin "1") (pinfunction "1_1") (pintype "passive"))
      (node (ref "C18") (pin "1") (pinfunction "1_1") (pintype "passive"))
      (node (ref "C19") (pin "1") (pinfunction "1_1") (pintype "passive"))
      (node (ref "C2") (pin "1") (pinfunction "1_1") (pintype "passive"))
      (node (ref "C20") (pin "1") (pinfunction "1_1") (pintype "passive"))
      (node (ref "C3") (pin "1") (pinfunction "1_1") (pintype "passive"))
      (node (ref "C4") (pin "1") (pinfunction "1_1") (pintype "passive"))
      (node (ref "C5") (pin "1") (pinfunction "1_1") (pintype "passive"))
      (node (ref "C6") (pin "1") (pinfunction "1_1") (pintype "passive"))
      (node (ref "C7") (pin "1") (pinfunction "1_1") (pintype "passive"))
      (node (ref "C8") (pin "2") (pinfunction "2_2") (pintype "passive"))
      (node (ref "C9") (pin "2") (pinfunction "2_2") (pintype "passive"))
      (node (ref "D1") (pin "2") (pinfunction "V-_2") (pintype "power_in"))
      (node (ref "D14") (pin "3") (pinfunction "A_3") (pintype "passive"))
      (node (ref "D2") (pin "2") (pinfunction "V-_2") (pintype "power_in"))
      (node (ref "J1") (pin "51") (pinfunction "51_51") (pintype "passive"))
      (node (ref "J1") (pin "53") (pinfunction "53_53") (pintype "passive"))
      (node (ref "J1") (pin "55") (pinfunction "55_55") (pintype "passive"))
      (node (ref "J1") (pin "57") (pinfunction "57_57") (pintype "passive"))
      (node (ref "J1") (pin "59") (pinfunction "59_59") (pintype "passive"))
      (node (ref "J1") (pin "60") (pinfunction "60_60") (pintype "passive"))
      (node (ref "J1") (pin "61") (pinfunction "61_61") (pintype "passive"))
      (node (ref "J1") (pin "62") (pinfunction "62_62") (pintype "passive"))
      (node (ref "J1") (pin "64") (pinfunction "64_64") (pintype "passive"))
      (node (ref "P1") (pin "1") (pinfunction "1_1") (pintype "passive"))
      (node (ref "P1") (pin "2") (pinfunction "2_2") (pintype "passive"))
      (node (ref "P1") (pin "39") (pinfunction "39_39") (pintype "passive"))
      (node (ref "P1") (pin "40") (pinfunction "40_40") (pintype "passive"))
      (node (ref "P2") (pin "14") (pinfunction "14_14") (pintype "passive"))
      (node (ref "P2") (pin "20") (pinfunction "20_20") (pintype "passive"))
      (node (ref "P2") (pin "25") (pinfunction "25_25") (pintype "passive"))
      (node (ref "P2") (pin "30") (pinfunction "30_30") (pintype "passive"))
      (node (ref "P2") (pin "34") (pinfunction "34_34") (pintype "passive"))
      (node (ref "P2") (pin "39") (pinfunction "39_39") (pintype "passive"))
      (node (ref "P2") (pin "6") (pinfunction "6_6") (pintype "passive"))
      (node (ref "P2") (pin "9") (pinfunction "9_9") (pintype "passive"))
      (node (ref "Q1") (pin "2") (pinfunction "S_2") (pintype "passive"))
      (node (ref "R44") (pin "1") (pinfunction "1_1") (pintype "passive"))
      (node (ref "U1") (pin "11") (pinfunction "GND_11") (pintype "power_in"))
      (node (ref "U10") (pin "1") (pinfunction "GND_1") (pintype "power_in"))
      (node (ref "U2") (pin "3") (pinfunction "GND_3") (pintype "passive"))
      (node (ref "U3") (pin "5") (pinfunction "GND_5") (pintype "power_in"))
      (node (ref "U4") (pin "11") (pinfunction "VSS_11") (pintype "power_in"))
      (node (ref "U4") (pin "23") (pinfunction "VSS_23") (pintype "power_in"))
      (node (ref "U4") (pin "27") (pinfunction "A0_27") (pintype "input"))
      (node (ref "U4") (pin "28") (pinfunction "A1_28") (pintype "input"))
      (node (ref "U4") (pin "29") (pinfunction "A2_29") (pintype "input"))
      (node (ref "U4") (pin "30") (pinfunction "~{OE}_30") (pintype "input"))
      (node (ref "U4") (pin "34") (pinfunction "VSS_34") (pintype "power_in"))
      (node (ref "U4") (pin "39") (pinfunction "VSS_39") (pintype "power_in"))
      (node (ref "U4") (pin "51") (pinfunction "VSS_51") (pintype "power_in"))
      (node (ref "U4") (pin "6") (pinfunction "VSS_6") (pintype "power_in"))
      (node (ref "U5") (pin "9") (pinfunction "GND_9") (pintype "power_in"))
      (node (ref "U6") (pin "9") (pinfunction "GND_9") (pintype "power_in"))
      (node (ref "U7") (pin "9") (pinfunction "GND_9") (pintype "power_in"))
      (node (ref "U8") (pin "11") (pinfunction "VSS_11") (pintype "power_in"))
      (node (ref "U8") (pin "23") (pinfunction "VSS_23") (pintype "power_in"))
      (node (ref "U8") (pin "28") (pinfunction "A1_28") (pintype "input"))
      (node (ref "U8") (pin "29") (pinfunction "A2_29") (pintype "input"))
      (node (ref "U8") (pin "30") (pinfunction "~{OE}_30") (pintype "input"))
      (node (ref "U8") (pin "34") (pinfunction "VSS_34") (pintype "power_in"))
      (node (ref "U8") (pin "39") (pinfunction "VSS_39") (pintype "power_in"))
      (node (ref "U8") (pin "51") (pinfunction "VSS_51") (pintype "power_in"))
      (node (ref "U8") (pin "6") (pinfunction "VSS_6") (pintype "power_in"))
      (node (ref "U9") (pin "1") (pinfunction "GND_1") (pintype "power_in"))
    )
    (net (code "129") (name "Net-(P1-Pad36)") (class "Default")
      (node (ref "P1") (pin "36") (pinfunction "36_36") (pintype "passive"))
      (node (ref "P1") (pin "38") (pinfunction "38_38") (pintype "passive"))
      (node (ref "R3") (pin "1") (pinfunction "1_1") (pintype "passive"))
    )
    (net (code "130") (name "Net-(P2-Pad1)") (class "Default")
      (node (ref "P2") (pin "1") (pinfunction "1_1") (pintype "passive"))
      (node (ref "R66") (pin "2") (pinfunction "2_2") (pintype "passive"))
    )
    (net (code "131") (name "Net-(P2-Pad2)") (class "Default")
      (node (ref "P2") (pin "2") (pinfunction "2_2") (pintype "passive"))
      (node (ref "P2") (pin "4") (pinfunction "4_4") (pintype "passive"))
      (node (ref "R2") (pin "1") (pinfunction "1_1") (pintype "passive"))
    )
    (net (code "132") (name "Net-(Q1-D)") (class "Default")
      (node (ref "Q1") (pin "3") (pinfunction "D_3") (pintype "passive"))
      (node (ref "R61") (pin "2") (pinfunction "2_2") (pintype "passive"))
      (node (ref "R62") (pin "2") (pinfunction "2_2") (pintype "passive"))
      (node (ref "U3") (pin "2") (pinfunction "~{RE}_2") (pintype "input"))
      (node (ref "U3") (pin "3") (pinfunction "DE_3") (pintype "input"))
    )
    (net (code "133") (name "Net-(Q1-G)") (class "Default")
      (node (ref "Q1") (pin "1") (pinfunction "G_1") (pintype "passive"))
      (node (ref "R63") (pin "2") (pinfunction "2_2") (pintype "passive"))
    )
    (net (code "134") (name "Net-(U1-OE)") (class "Default")
      (node (ref "R1") (pin "2") (pinfunction "2_2") (pintype "passive"))
      (node (ref "U1") (pin "10") (pinfunction "OE_10") (pintype "input"))
    )
    (net (code "135") (name "Net-(U3-A)") (class "Default")
      (node (ref "R64") (pin "1") (pinfunction "1_1") (pintype "passive"))
      (node (ref "U3") (pin "6") (pinfunction "A_6") (pintype "bidirectional"))
    )
    (net (code "136") (name "Net-(U3-B)") (class "Default")
      (node (ref "R67") (pin "1") (pinfunction "1_1") (pintype "passive"))
      (node (ref "U3") (pin "7") (pinfunction "B_7") (pintype "bidirectional"))
    )
    (net (code "137") (name "Net-(U4A-IO2_6)") (class "Default")
      (node (ref "TP1") (pin "1") (pintype "passive"))
      (node (ref "U4") (pin "33") (pinfunction "IO2_6_33") (pintype "bidirectional"))
    )
    (net (code "138") (name "Net-(U4A-IO2_7)") (class "Default")
      (node (ref "TP2") (pin "1") (pintype "passive"))
      (node (ref "U4") (pin "35") (pinfunction "IO2_7_35") (pintype "bidirectional"))
    )
    (net (code "139") (name "Net-(U8A-IO2_5)") (class "Default")
      (node (ref "TP3") (pin "1") (pintype "passive"))
      (node (ref "U8") (pin "32") (pinfunction "IO2_5_32") (pintype "bidirectional"))
    )
    (net (code "140") (name "Net-(U8A-IO2_6)") (class "Default")
      (node (ref "TP4") (pin "1") (pintype "passive"))
      (node (ref "U8") (pin "33") (pinfunction "IO2_6_33") (pintype "bidirectional"))
    )
    (net (code "141") (name "Net-(U8A-IO2_7)") (class "Default")
      (node (ref "TP5") (pin "1") (pintype "passive"))
      (node (ref "U8") (pin "35") (pinfunction "IO2_7_35") (pintype "bidirectional"))
    )
    (net (code "142") (name "Net-(U8A-IO4_3)") (class "Default")
      (node (ref "TP6") (pin "1") (pintype "passive"))
      (node (ref "U8") (pin "49") (pinfunction "IO4_3_49") (pintype "bidirectional"))
    )
    (net (code "143") (name "Net-(U8A-IO4_4)") (class "Default")
      (node (ref "TP7") (pin "1") (pintype "passive"))
      (node (ref "U8") (pin "50") (pinfunction "IO4_4_50") (pintype "bidirectional"))
    )
    (net (code "144") (name "Net-(U8A-IO4_5)") (class "Default")
      (node (ref "TP8") (pin "1") (pintype "passive"))
      (node (ref "U8") (pin "52") (pinfunction "IO4_5_52") (pintype "bidirectional"))
    )
    (net (code "145") (name "Net-(U8B-A0)") (class "Default")
      (node (ref "R8") (pin "2") (pinfunction "2_2") (pintype "passive"))
      (node (ref "U8") (pin "27") (pinfunction "A0_27") (pintype "input"))
    )
    (net (code "146") (name "SYS_DCIN") (class "Default")
      (node (ref "C15") (pin "1") (pinfunction "1_1") (pintype "passive"))
      (node (ref "C16") (pin "2") (pinfunction "2_2") (pintype "passive"))
      (node (ref "L1") (pin "2") (pinfunction "2_2") (pintype "passive"))
      (node (ref "R3") (pin "2") (pinfunction "2_2") (pintype "passive"))
      (node (ref "U9") (pin "3") (pinfunction "VIN_3") (pintype "power_in"))
    )
    (net (code "147") (name "VDC_1V8") (class "Default")
      (node (ref "C1") (pin "2") (pinfunction "2_2") (pintype "passive"))
      (node (ref "C3") (pin "2") (pinfunction "2_2") (pintype "passive"))
      (node (ref "P1") (pin "35") (pinfunction "35_35") (pintype "passive"))
      (node (ref "R1") (pin "1") (pinfunction "1_1") (pintype "passive"))
      (node (ref "U1") (pin "2") (pinfunction "VCCA_2") (pintype "power_in"))
    )
    (net (code "148") (name "VDC_3V3") (class "Default")
      (node (ref "C11") (pin "2") (pinfunction "2_2") (pintype "passive"))
      (node (ref "C12") (pin "2") (pinfunction "2_2") (pintype "passive"))
      (node (ref "C19") (pin "2") (pinfunction "2_2") (pintype "passive"))
      (node (ref "C2") (pin "2") (pinfunction "2_2") (pintype "passive"))
      (node (ref "C20") (pin "2") (pinfunction "2_2") (pintype "passive"))
      (node (ref "C4") (pin "2") (pinfunction "2_2") (pintype "passive"))
      (node (ref "C5") (pin "2") (pinfunction "2_2") (pintype "passive"))
      (node (ref "C6") (pin "2") (pinfunction "2_2") (pintype "passive"))
      (node (ref "C7") (pin "2") (pinfunction "2_2") (pintype "passive"))
      (node (ref "R4") (pin "1") (pinfunction "1_1") (pintype "passive"))
      (node (ref "R5") (pin "1") (pinfunction "1_1") (pintype "passive"))
      (node (ref "R6") (pin "1") (pinfunction "1_1") (pintype "passive"))
      (node (ref "R61") (pin "1") (pinfunction "1_1") (pintype "passive"))
      (node (ref "R65") (pin "1") (pinfunction "1_1") (pintype "passive"))
      (node (ref "R66") (pin "1") (pinfunction "1_1") (pintype "passive"))
      (node (ref "R7") (pin "1") (pinfunction "1_1") (pintype "passive"))
      (node (ref "R8") (pin "1") (pinfunction "1_1") (pintype "passive"))
      (node (ref "R9") (pin "1") (pinfunction "1_1") (pintype "passive"))
      (node (ref "U1") (pin "19") (pinfunction "VCCB_19") (pintype "power_in"))
      (node (ref "U10") (pin "4") (pinfunction "VOUT_4") (pintype "power_in"))
      (node (ref "U2") (pin "8") (pinfunction "VDD_8") (pintype "passive"))
      (node (ref "U3") (pin "8") (pinfunction "VCC_8") (pintype "power_in"))
      (node (ref "U4") (pin "18") (pinfunction "VDD_18") (pintype "power_in"))
      (node (ref "U4") (pin "46") (pinfunction "VDD_46") (pintype "power_in"))
      (node (ref "U8") (pin "18") (pinfunction "VDD_18") (pintype "power_in"))
      (node (ref "U8") (pin "46") (pinfunction "VDD_46") (pintype "power_in"))
    )
    (net (code "149") (name "VDC_5V0") (class "Default")
      (node (ref "C17") (pin "2") (pinfunction "2_2") (pintype "passive"))
      (node (ref "C18") (pin "2") (pinfunction "2_2") (pintype "passive"))
      (node (ref "R2") (pin "2") (pinfunction "2_2") (pintype "passive"))
      (node (ref "U10") (pin "3") (pinfunction "VIN_3") (pintype "power_in"))
      (node (ref "U9") (pin "4") (pinfunction "VOUT_4") (pintype "power_in"))
    )
    (net (code "150") (name "VDC_15V") (class "Default")
      (node (ref "C13") (pin "1") (pinfunction "1_1") (pintype "passive"))
      (node (ref "C14") (pin "1") (pinfunction "1_1") (pintype "passive"))
      (node (ref "D2") (pin "1") (pinfunction "V+_1") (pintype "power_in"))
      (node (ref "J1") (pin "63") (pinfunction "63_63") (pintype "passive"))
      (node (ref "J1") (pin "65") (pinfunction "65_65") (pintype "passive"))
      (node (ref "J1") (pin "66") (pinfunction "66_66") (pintype "passive"))
      (node (ref "J1") (pin "68") (pinfunction "68_68") (pintype "passive"))
      (node (ref "J1") (pin "70") (pinfunction "70_70") (pintype "passive"))
      (node (ref "L1") (pin "1") (pinfunction "1_1") (pintype "passive"))
    )
    (net (code "151") (name "VDC_22V") (class "Default")
      (node (ref "C10") (pin "1") (pinfunction "1_1") (pintype "passive"))
      (node (ref "C8") (pin "1") (pinfunction "1_1") (pintype "passive"))
      (node (ref "C9") (pin "1") (pinfunction "1_1") (pintype "passive"))
      (node (ref "D1") (pin "1") (pinfunction "V+_1") (pintype "power_in"))
      (node (ref "J1") (pin "67") (pinfunction "67_67") (pintype "passive"))
      (node (ref "J1") (pin "69") (pinfunction "69_69") (pintype "passive"))
      (node (ref "U5") (pin "10") (pinfunction "COM_10") (pintype "passive"))
      (node (ref "U6") (pin "10") (pinfunction "COM_10") (pintype "passive"))
      (node (ref "U7") (pin "10") (pinfunction "COM_10") (pintype "passive"))
    )
    (net (code "152") (name "unconnected-(J1-Pad8)") (class "Default")
      (node (ref "J1") (pin "8") (pinfunction "8_8") (pintype "passive"))
    )
    (net (code "153") (name "unconnected-(J1-Pad10)") (class "Default")
      (node (ref "J1") (pin "10") (pinfunction "10_10") (pintype "passive"))
    )
    (net (code "154") (name "unconnected-(J1-Pad34)") (class "Default")
      (node (ref "J1") (pin "34") (pinfunction "34_34") (pintype "passive"))
    )
    (net (code "155") (name "unconnected-(J1-Pad36)") (class "Default")
      (node (ref "J1") (pin "36") (pinfunction "36_36") (pintype "passive"))
    )
    (net (code "156") (name "unconnected-(J1-Pad38)") (class "Default")
      (node (ref "J1") (pin "38") (pinfunction "38_38") (pintype "passive"))
    )
    (net (code "157") (name "unconnected-(J1-Pad40)") (class "Default")
      (node (ref "J1") (pin "40") (pinfunction "40_40") (pintype "passive"))
    )
    (net (code "158") (name "unconnected-(J1-Pad42)") (class "Default")
      (node (ref "J1") (pin "42") (pinfunction "42_42") (pintype "passive"))
    )
    (net (code "159") (name "unconnected-(J1-Pad43)") (class "Default")
      (node (ref "J1") (pin "43") (pinfunction "43_43") (pintype "passive"))
    )
    (net (code "160") (name "unconnected-(J1-Pad44)") (class "Default")
      (node (ref "J1") (pin "44") (pinfunction "44_44") (pintype "passive"))
    )
    (net (code "161") (name "unconnected-(J1-Pad45)") (class "Default")
      (node (ref "J1") (pin "45") (pinfunction "45_45") (pintype "passive"))
    )
    (net (code "162") (name "unconnected-(J1-Pad46)") (class "Default")
      (node (ref "J1") (pin "46") (pinfunction "46_46") (pintype "passive"))
    )
    (net (code "163") (name "unconnected-(J1-Pad47)") (class "Default")
      (node (ref "J1") (pin "47") (pinfunction "47_47") (pintype "passive"))
    )
    (net (code "164") (name "unconnected-(J1-Pad48)") (class "Default")
      (node (ref "J1") (pin "48") (pinfunction "48_48") (pintype "passive"))
    )
    (net (code "165") (name "unconnected-(J1-Pad49)") (class "Default")
      (node (ref "J1") (pin "49") (pinfunction "49_49") (pintype "passive"))
    )
    (net (code "166") (name "unconnected-(J1-Pad54)") (class "Default")
      (node (ref "J1") (pin "54") (pinfunction "54_54") (pintype "passive"))
    )
    (net (code "167") (name "unconnected-(J1-Pad56)") (class "Default")
      (node (ref "J1") (pin "56") (pinfunction "56_56") (pintype "passive"))
    )
    (net (code "168") (name "unconnected-(J1-Pad58)") (class "Default")
      (node (ref "J1") (pin "58") (pinfunction "58_58") (pintype "passive"))
    )
    (net (code "169") (name "unconnected-(J1-PadMH1)") (class "Default")
      (node (ref "J1") (pin "MH1") (pinfunction "MH1_MH1") (pintype "passive+no_connect"))
    )
    (net (code "170") (name "unconnected-(J1-PadMH2)") (class "Default")
      (node (ref "J1") (pin "MH2") (pinfunction "MH2_MH2") (pintype "passive+no_connect"))
    )
    (net (code "171") (name "unconnected-(P1-Pad3)") (class "Default")
      (node (ref "P1") (pin "3") (pinfunction "3_3") (pintype "passive"))
    )
    (net (code "172") (name "unconnected-(P1-Pad6)") (class "Default")
      (node (ref "P1") (pin "6") (pinfunction "6_6") (pintype "passive"))
    )
    (net (code "173") (name "unconnected-(P1-Pad8)") (class "Default")
      (node (ref "P1") (pin "8") (pinfunction "8_8") (pintype "passive"))
    )
    (net (code "174") (name "unconnected-(P1-Pad10)") (class "Default")
      (node (ref "P1") (pin "10") (pinfunction "10_10") (pintype "passive"))
    )
    (net (code "175") (name "unconnected-(P1-Pad11)") (class "Default")
      (node (ref "P1") (pin "11") (pinfunction "11_11") (pintype "passive"))
    )
    (net (code "176") (name "unconnected-(P1-Pad12)") (class "Default")
      (node (ref "P1") (pin "12") (pinfunction "12_12") (pintype "passive"))
    )
    (net (code "177") (name "unconnected-(P1-Pad13)") (class "Default")
      (node (ref "P1") (pin "13") (pinfunction "13_13") (pintype "passive"))
    )
    (net (code "178") (name "unconnected-(P1-Pad14)") (class "Default")
      (node (ref "P1") (pin "14") (pinfunction "14_14") (pintype "passive"))
    )
    (net (code "179") (name "unconnected-(P1-Pad16)") (class "Default")
      (node (ref "P1") (pin "16") (pinfunction "16_16") (pintype "passive"))
    )
    (net (code "180") (name "unconnected-(P1-Pad18)") (class "Default")
      (node (ref "P1") (pin "18") (pinfunction "18_18") (pintype "passive"))
    )
    (net (code "181") (name "unconnected-(P1-Pad19)") (class "Default")
      (node (ref "P1") (pin "19") (pinfunction "19_19") (pintype "passive"))
    )
    (net (code "182") (name "unconnected-(P1-Pad20)") (class "Default")
      (node (ref "P1") (pin "20") (pinfunction "20_20") (pintype "passive"))
    )
    (net (code "183") (name "unconnected-(P1-Pad21)") (class "Default")
      (node (ref "P1") (pin "21") (pinfunction "21_21") (pintype "passive"))
    )
    (net (code "184") (name "unconnected-(P1-Pad22)") (class "Default")
      (node (ref "P1") (pin "22") (pinfunction "22_22") (pintype "passive"))
    )
    (net (code "185") (name "unconnected-(P1-Pad23)") (class "Default")
      (node (ref "P1") (pin "23") (pinfunction "23_23") (pintype "passive"))
    )
    (net (code "186") (name "unconnected-(P1-Pad24)") (class "Default")
      (node (ref "P1") (pin "24") (pinfunction "24_24") (pintype "passive"))
    )
    (net (code "187") (name "unconnected-(P1-Pad28)") (class "Default")
      (node (ref "P1") (pin "28") (pinfunction "28_28") (pintype "passive"))
    )
    (net (code "188") (name "unconnected-(P1-Pad29)") (class "Default")
      (node (ref "P1") (pin "29") (pinfunction "29_29") (pintype "passive"))
    )
    (net (code "189") (name "unconnected-(P1-Pad30)") (class "Default")
      (node (ref "P1") (pin "30") (pinfunction "30_30") (pintype "passive"))
    )
    (net (code "190") (name "unconnected-(P1-Pad31)") (class "Default")
      (node (ref "P1") (pin "31") (pinfunction "31_31") (pintype "passive"))
    )
    (net (code "191") (name "unconnected-(P1-Pad32)") (class "Default")
      (node (ref "P1") (pin "32") (pinfunction "32_32") (pintype "passive"))
    )
    (net (code "192") (name "unconnected-(P1-Pad33)") (class "Default")
      (node (ref "P1") (pin "33") (pinfunction "33_33") (pintype "passive"))
    )
    (net (code "193") (name "unconnected-(P1-Pad34)") (class "Default")
      (node (ref "P1") (pin "34") (pinfunction "34_34") (pintype "passive"))
    )
    (net (code "194") (name "unconnected-(P1-Pad37)") (class "Default")
      (node (ref "P1") (pin "37") (pinfunction "37_37") (pintype "passive"))
    )
    (net (code "195") (name "unconnected-(P2-Pad12)") (class "Default")
      (node (ref "P2") (pin "12") (pinfunction "12_12") (pintype "passive"))
    )
    (net (code "196") (name "unconnected-(P2-Pad13)") (class "Default")
      (node (ref "P2") (pin "13") (pinfunction "13_13") (pintype "passive"))
    )
    (net (code "197") (name "unconnected-(P2-Pad15)") (class "Default")
      (node (ref "P2") (pin "15") (pinfunction "15_15") (pintype "passive"))
    )
    (net (code "198") (name "unconnected-(P2-Pad17)") (class "Default")
      (node (ref "P2") (pin "17") (pinfunction "17_17") (pintype "passive"))
    )
    (net (code "199") (name "unconnected-(P2-Pad19)") (class "Default")
      (node (ref "P2") (pin "19") (pinfunction "19_19") (pintype "passive"))
    )
    (net (code "200") (name "unconnected-(P2-Pad21)") (class "Default")
      (node (ref "P2") (pin "21") (pinfunction "21_21") (pintype "passive"))
    )
    (net (code "201") (name "unconnected-(P2-Pad23)") (class "Default")
      (node (ref "P2") (pin "23") (pinfunction "23_23") (pintype "passive"))
    )
    (net (code "202") (name "unconnected-(P2-Pad24)") (class "Default")
      (node (ref "P2") (pin "24") (pinfunction "24_24") (pintype "passive"))
    )
    (net (code "203") (name "unconnected-(P2-Pad26)") (class "Default")
      (node (ref "P2") (pin "26") (pinfunction "26_26") (pintype "passive"))
    )
    (net (code "204") (name "unconnected-(P2-Pad27)") (class "Default")
      (node (ref "P2") (pin "27") (pinfunction "27_27") (pintype "passive"))
    )
    (net (code "205") (name "unconnected-(P2-Pad28)") (class "Default")
      (node (ref "P2") (pin "28") (pinfunction "28_28") (pintype "passive"))
    )
    (net (code "206") (name "unconnected-(P2-Pad29)") (class "Default")
      (node (ref "P2") (pin "29") (pinfunction "29_29") (pintype "passive"))
    )
    (net (code "207") (name "unconnected-(P2-Pad31)") (class "Default")
      (node (ref "P2") (pin "31") (pinfunction "31_31") (pintype "passive"))
    )
    (net (code "208") (name "unconnected-(P2-Pad32)") (class "Default")
      (node (ref "P2") (pin "32") (pinfunction "32_32") (pintype "passive"))
    )
    (net (code "209") (name "unconnected-(P2-Pad33)") (class "Default")
      (node (ref "P2") (pin "33") (pinfunction "33_33") (pintype "passive"))
    )
    (net (code "210") (name "unconnected-(P2-Pad35)") (class "Default")
      (node (ref "P2") (pin "35") (pinfunction "35_35") (pintype "passive"))
    )
    (net (code "211") (name "unconnected-(P2-Pad36)") (class "Default")
      (node (ref "P2") (pin "36") (pinfunction "36_36") (pintype "passive"))
    )
    (net (code "212") (name "unconnected-(P2-Pad37)") (class "Default")
      (node (ref "P2") (pin "37") (pinfunction "37_37") (pintype "passive"))
    )
    (net (code "213") (name "unconnected-(P2-Pad38)") (class "Default")
      (node (ref "P2") (pin "38") (pinfunction "38_38") (pintype "passive"))
    )
    (net (code "214") (name "unconnected-(P2-Pad40)") (class "Default")
      (node (ref "P2") (pin "40") (pinfunction "40_40") (pintype "passive"))
    )
    (net (code "215") (name "unconnected-(U2-ADDR-Pad1)") (class "Default")
      (node (ref "U2") (pin "1") (pinfunction "ADDR_1") (pintype "passive+no_connect"))
    )
    (net (code "216") (name "unconnected-(U2-AIN3-Pad7)") (class "Default")
      (node (ref "U2") (pin "7") (pinfunction "AIN3_7") (pintype "passive+no_connect"))
    )
    (net (code "217") (name "unconnected-(U2-ALERT{slash}RDY-Pad2)") (class "Default")
      (node (ref "U2") (pin "2") (pinfunction "ALERT/RDY_2") (pintype "passive+no_connect"))
    )
    (net (code "218") (name "unconnected-(U7-1B-Pad1)") (class "Default")
      (node (ref "U7") (pin "1") (pinfunction "1B_1") (pintype "input+no_connect"))
    )
    (net (code "219") (name "unconnected-(U7-1C-Pad18)") (class "Default")
      (node (ref "U7") (pin "18") (pinfunction "1C_18") (pintype "output+no_connect"))
    )
    (net (code "220") (name "unconnected-(U7-2B-Pad2)") (class "Default")
      (node (ref "U7") (pin "2") (pinfunction "2B_2") (pintype "input+no_connect"))
    )
    (net (code "221") (name "unconnected-(U7-2C-Pad17)") (class "Default")
      (node (ref "U7") (pin "17") (pinfunction "2C_17") (pintype "output+no_connect"))
    )
    (net (code "222") (name "unconnected-(U7-3B-Pad3)") (class "Default")
      (node (ref "U7") (pin "3") (pinfunction "3B_3") (pintype "input+no_connect"))
    )
    (net (code "223") (name "unconnected-(U7-3C-Pad16)") (class "Default")
      (node (ref "U7") (pin "16") (pinfunction "3C_16") (pintype "output+no_connect"))
    )
    (net (code "224") (name "unconnected-(U8A-IO4_6-Pad53)") (class "Default")
      (node (ref "U8") (pin "53") (pinfunction "IO4_6_53") (pintype "bidirectional+no_connect"))
    )
    (net (code "225") (name "unconnected-(U8A-IO4_7-Pad54)") (class "Default")
      (node (ref "U8") (pin "54") (pinfunction "IO4_7_54") (pintype "bidirectional+no_connect"))
    )
  )
)
